# Active_LPF_Sch.net
KiCad netlist of a schematic drawn in Altium Designer
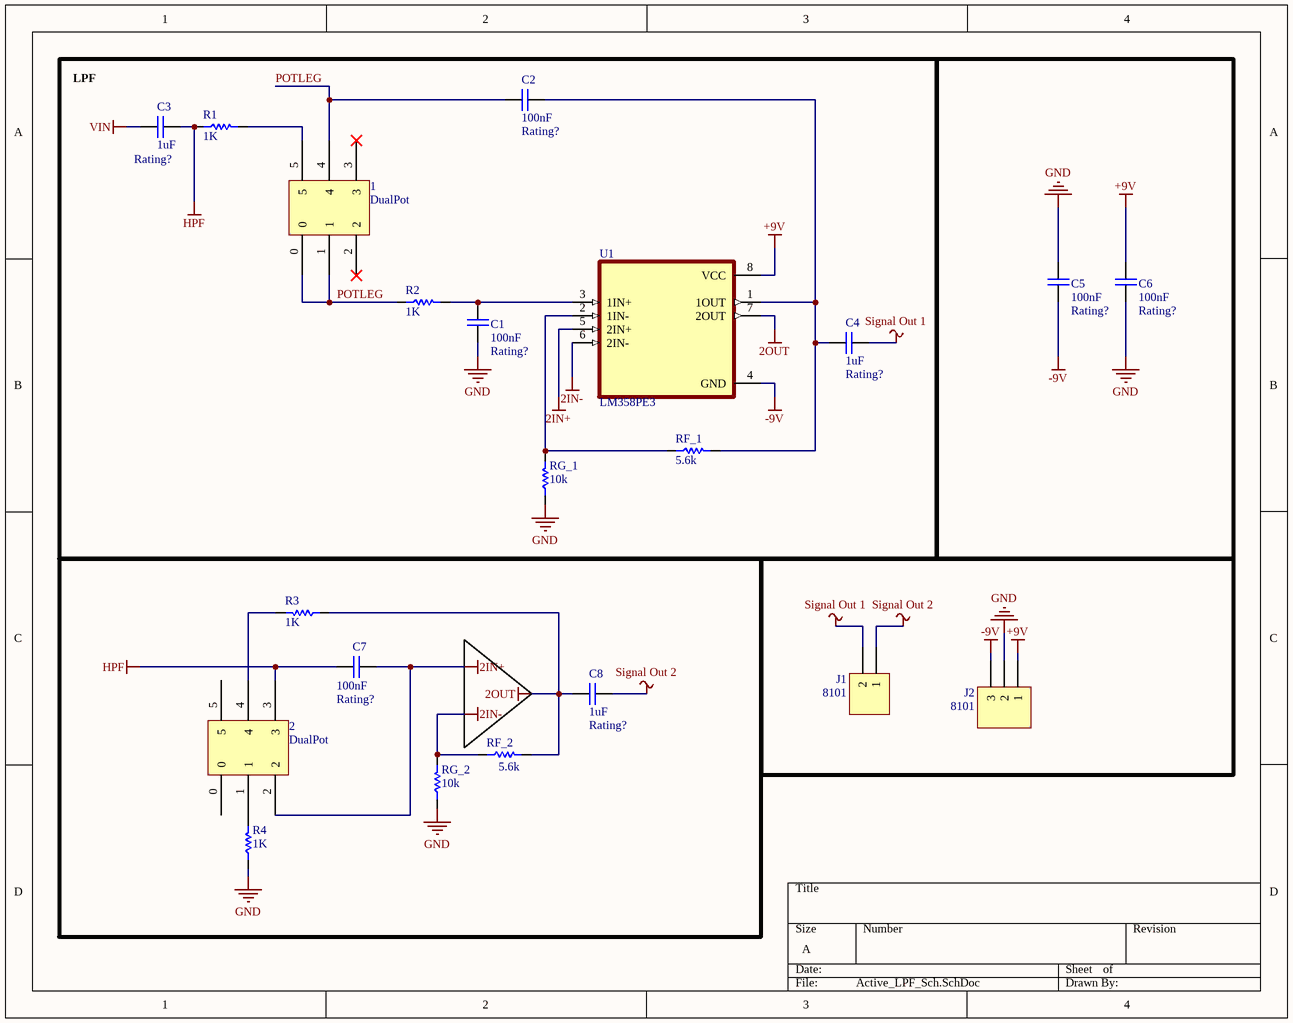
[diagram p0: Active_LPF_Sch.SchDoc]

(export (version "E")
  (design (tool "Eeschema 10.0.6"))
  (components
    (comp (ref "1") (value "DualPot") (footprint "DualPot") (libsource (lib "DualPot") (part "DualPot")))
    (comp (ref "2") (value "DualPot") (footprint "DualPot") (libsource (lib "DualPot") (part "DualPot")))
    (comp (ref "C1")
      (value "100nF")
      (footprint "Cap")
      (description "Multi layer capacitor")
      (fields (field (name "RATING") "Rating?") (field (name "VALIDATION") "Valid"))
      (libsource (lib "aKaReZa") (part "Cap_Multi_THT"))
    )
    (comp (ref "C2")
      (value "100nF")
      (footprint "Cap")
      (description "Multi layer capacitor")
      (fields (field (name "RATING") "Rating?") (field (name "VALIDATION") "Valid"))
      (libsource (lib "aKaReZa") (part "Cap_Multi_THT"))
    )
    (comp (ref "C3")
      (value "1uF")
      (footprint "Cap")
      (description "Multi layer capacitor")
      (fields (field (name "RATING") "Rating?") (field (name "VALIDATION") "Valid"))
      (libsource (lib "aKaReZa") (part "Cap_Multi_THT"))
    )
    (comp (ref "C4")
      (value "1uF")
      (footprint "Cap")
      (description "Multi layer capacitor")
      (fields (field (name "RATING") "Rating?") (field (name "VALIDATION") "Valid"))
      (libsource (lib "aKaReZa") (part "Cap_Multi_THT"))
    )
    (comp (ref "C5")
      (value "100nF")
      (footprint "Cap")
      (description "Multi layer capacitor")
      (fields (field (name "RATING") "Rating?") (field (name "VALIDATION") "Valid"))
      (libsource (lib "aKaReZa") (part "Cap_Multi_THT"))
    )
    (comp (ref "C6")
      (value "100nF")
      (footprint "Cap")
      (description "Multi layer capacitor")
      (fields (field (name "RATING") "Rating?") (field (name "VALIDATION") "Valid"))
      (libsource (lib "aKaReZa") (part "Cap_Multi_THT"))
    )
    (comp (ref "C7")
      (value "100nF")
      (footprint "Cap")
      (description "Multi layer capacitor")
      (fields (field (name "RATING") "Rating?") (field (name "VALIDATION") "Valid"))
      (libsource (lib "aKaReZa") (part "Cap_Multi_THT"))
    )
    (comp (ref "C8")
      (value "1uF")
      (footprint "Cap")
      (description "Multi layer capacitor")
      (fields (field (name "RATING") "Rating?") (field (name "VALIDATION") "Valid"))
      (libsource (lib "aKaReZa") (part "Cap_Multi_THT"))
    )
    (comp (ref "J1")
      (value "2")
      (footprint "HDR_THT_2F_2.54mm")
      (description "Header, single row, 2 pin")
      (fields (field (name "INFLOW") "8101") (field (name "VALIDATION") "NT"))
      (libsource (lib "aKaReZa") (part "Con_FPH_2x1_V_THT_2.54"))
    )
    (comp (ref "J2")
      (value "3")
      (footprint "HDR_THT_3F_2.54mm")
      (description "Header, single row, 3 pin")
      (fields (field (name "INFLOW") "8101") (field (name "VALIDATION") "NT"))
      (libsource (lib "aKaReZa") (part "Con_FPH_3x1_V_THT_2.54"))
    )
    (comp (ref "R1")
      (value "1K")
      (footprint "Res-(1/4)")
      (description "Resistor")
      (fields (field (name "VALIDATION") "Valid"))
      (libsource (lib "aKaReZa") (part "Res_THT"))
    )
    (comp (ref "R2")
      (value "1K")
      (footprint "Res-(1/4)")
      (description "Resistor")
      (fields (field (name "VALIDATION") "Valid"))
      (libsource (lib "aKaReZa") (part "Res_THT"))
    )
    (comp (ref "R3")
      (value "1K")
      (footprint "Res-(1/4)")
      (description "Resistor")
      (fields (field (name "VALIDATION") "Valid"))
      (libsource (lib "aKaReZa") (part "Res_THT"))
    )
    (comp (ref "R4")
      (value "1K")
      (footprint "Res-(1/4)")
      (description "Resistor")
      (fields (field (name "VALIDATION") "Valid"))
      (libsource (lib "aKaReZa") (part "Res_THT"))
    )
    (comp (ref "RF_1")
      (value "5.6k")
      (footprint "Res-(1/4)")
      (description "Resistor")
      (fields (field (name "VALIDATION") "Valid"))
      (libsource (lib "aKaReZa") (part "Res_THT"))
    )
    (comp (ref "RF_2")
      (value "5.6k")
      (footprint "Res-(1/4)")
      (description "Resistor")
      (fields (field (name "VALIDATION") "Valid"))
      (libsource (lib "aKaReZa") (part "Res_THT"))
    )
    (comp (ref "RG_1")
      (value "10k")
      (footprint "Res-(1/4)")
      (description "Resistor")
      (fields (field (name "VALIDATION") "Valid"))
      (libsource (lib "aKaReZa") (part "Res_THT"))
    )
    (comp (ref "RG_2")
      (value "10k")
      (footprint "Res-(1/4)")
      (description "Resistor")
      (fields (field (name "VALIDATION") "Valid"))
      (libsource (lib "aKaReZa") (part "Res_THT"))
    )
    (comp (ref "U1")
      (value "LM358PE3")
      (footprint "DIP794W45P254L959H508Q8")
      (description "Dual, 30-V, 700-kHz operational amplifier")
      (fields (field (name "MF") "Texas Instruments"))
      (libsource (lib "LM358PE3") (part "LM358PE3"))
    )
  )
  (nets
    (net (code "1") (name "+9V") (class "Default")
      (node (ref "C6") (pin "2") (pinfunction "2_2") (pintype "passive"))
      (node (ref "J2") (pin "1") (pinfunction "1_1") (pintype "passive"))
      (node (ref "U1") (pin "8") (pinfunction "VCC_8") (pintype "power_in"))
    )
    (net (code "2") (name "-9V") (class "Default")
      (node (ref "C5") (pin "1") (pinfunction "1_1") (pintype "passive"))
      (node (ref "J2") (pin "3") (pinfunction "3_3") (pintype "passive"))
      (node (ref "U1") (pin "4") (pinfunction "GND_4") (pintype "power_in"))
    )
    (net (code "3") (name "/POTLEG") (class "Default")
      (node (ref "1") (pin "0") (pinfunction "0_0") (pintype "passive"))
      (node (ref "1") (pin "1") (pinfunction "1_1") (pintype "passive"))
      (node (ref "1") (pin "4") (pinfunction "4_4") (pintype "passive"))
      (node (ref "C2") (pin "1") (pinfunction "1_1") (pintype "passive"))
      (node (ref "R2") (pin "1") (pinfunction "1_1") (pintype "passive"))
    )
    (net (code "4") (name "2IN+") (class "Default")
      (node (ref "2") (pin "2") (pinfunction "2_2") (pintype "passive"))
      (node (ref "C7") (pin "2") (pinfunction "2_2") (pintype "passive"))
      (node (ref "U1") (pin "5") (pinfunction "2IN+_5") (pintype "input"))
    )
    (net (code "5") (name "2IN-") (class "Default")
      (node (ref "RF_2") (pin "1") (pinfunction "1_1") (pintype "passive"))
      (node (ref "RG_2") (pin "2") (pinfunction "2_2") (pintype "passive"))
      (node (ref "U1") (pin "6") (pinfunction "2IN-_6") (pintype "input"))
    )
    (net (code "6") (name "2OUT") (class "Default")
      (node (ref "C8") (pin "1") (pinfunction "1_1") (pintype "passive"))
      (node (ref "R3") (pin "1") (pinfunction "1_1") (pintype "passive"))
      (node (ref "RF_2") (pin "2") (pinfunction "2_2") (pintype "passive"))
      (node (ref "U1") (pin "7") (pinfunction "2OUT_7") (pintype "output"))
    )
    (net (code "7") (name "GND") (class "Default")
      (node (ref "C1") (pin "2") (pinfunction "2_2") (pintype "passive"))
      (node (ref "C5") (pin "2") (pinfunction "2_2") (pintype "passive"))
      (node (ref "C6") (pin "1") (pinfunction "1_1") (pintype "passive"))
      (node (ref "J2") (pin "2") (pinfunction "2_2") (pintype "passive"))
      (node (ref "R4") (pin "1") (pinfunction "1_1") (pintype "passive"))
      (node (ref "RG_1") (pin "1") (pinfunction "1_1") (pintype "passive"))
      (node (ref "RG_2") (pin "1") (pinfunction "1_1") (pintype "passive"))
    )
    (net (code "8") (name "HPF") (class "Default")
      (node (ref "2") (pin "3") (pinfunction "3_3") (pintype "passive"))
      (node (ref "C3") (pin "2") (pinfunction "2_2") (pintype "passive"))
      (node (ref "C7") (pin "1") (pinfunction "1_1") (pintype "passive"))
      (node (ref "R1") (pin "1") (pinfunction "1_1") (pintype "passive"))
    )
    (net (code "9") (name "Net-(1-Pad5)") (class "Default")
      (node (ref "1") (pin "5") (pinfunction "5_5") (pintype "passive"))
      (node (ref "R1") (pin "2") (pinfunction "2_2") (pintype "passive"))
    )
    (net (code "10") (name "Net-(2-Pad1)") (class "Default")
      (node (ref "2") (pin "1") (pinfunction "1_1") (pintype "passive"))
      (node (ref "R4") (pin "2") (pinfunction "2_2") (pintype "passive"))
    )
    (net (code "11") (name "Net-(2-Pad4)") (class "Default")
      (node (ref "2") (pin "4") (pinfunction "4_4") (pintype "passive"))
      (node (ref "R3") (pin "2") (pinfunction "2_2") (pintype "passive"))
    )
    (net (code "12") (name "Net-(U1-1IN+)") (class "Default")
      (node (ref "C1") (pin "1") (pinfunction "1_1") (pintype "passive"))
      (node (ref "R2") (pin "2") (pinfunction "2_2") (pintype "passive"))
      (node (ref "U1") (pin "3") (pinfunction "1IN+_3") (pintype "input"))
    )
    (net (code "13") (name "Net-(U1-1IN-)") (class "Default")
      (node (ref "RF_1") (pin "1") (pinfunction "1_1") (pintype "passive"))
      (node (ref "RG_1") (pin "2") (pinfunction "2_2") (pintype "passive"))
      (node (ref "U1") (pin "2") (pinfunction "1IN-_2") (pintype "input"))
    )
    (net (code "14") (name "Net-(U1-1OUT)") (class "Default")
      (node (ref "C2") (pin "2") (pinfunction "2_2") (pintype "passive"))
      (node (ref "C4") (pin "1") (pinfunction "1_1") (pintype "passive"))
      (node (ref "RF_1") (pin "2") (pinfunction "2_2") (pintype "passive"))
      (node (ref "U1") (pin "1") (pinfunction "1OUT_1") (pintype "output"))
    )
    (net (code "15") (name "Signal Out 1") (class "Default")
      (node (ref "C4") (pin "2") (pinfunction "2_2") (pintype "passive"))
      (node (ref "J1") (pin "2") (pinfunction "2_2") (pintype "passive"))
    )
    (net (code "16") (name "Signal Out 2") (class "Default")
      (node (ref "C8") (pin "2") (pinfunction "2_2") (pintype "passive"))
      (node (ref "J1") (pin "1") (pinfunction "1_1") (pintype "passive"))
    )
    (net (code "17") (name "VIN") (class "Default")
      (node (ref "C3") (pin "1") (pinfunction "1_1") (pintype "passive"))
    )
    (net (code "18") (name "unconnected-(1-Pad2)") (class "Default")
      (node (ref "1") (pin "2") (pinfunction "2_2") (pintype "passive+no_connect"))
    )
    (net (code "19") (name "unconnected-(1-Pad3)") (class "Default")
      (node (ref "1") (pin "3") (pinfunction "3_3") (pintype "passive+no_connect"))
    )
    (net (code "20") (name "unconnected-(2-Pad0)") (class "Default")
      (node (ref "2") (pin "0") (pinfunction "0_0") (pintype "passive"))
    )
    (net (code "21") (name "unconnected-(2-Pad5)") (class "Default")
      (node (ref "2") (pin "5") (pinfunction "5_5") (pintype "passive"))
    )
  )
)
